# main.net
KiCad netlist of a schematic drawn in EAGLE
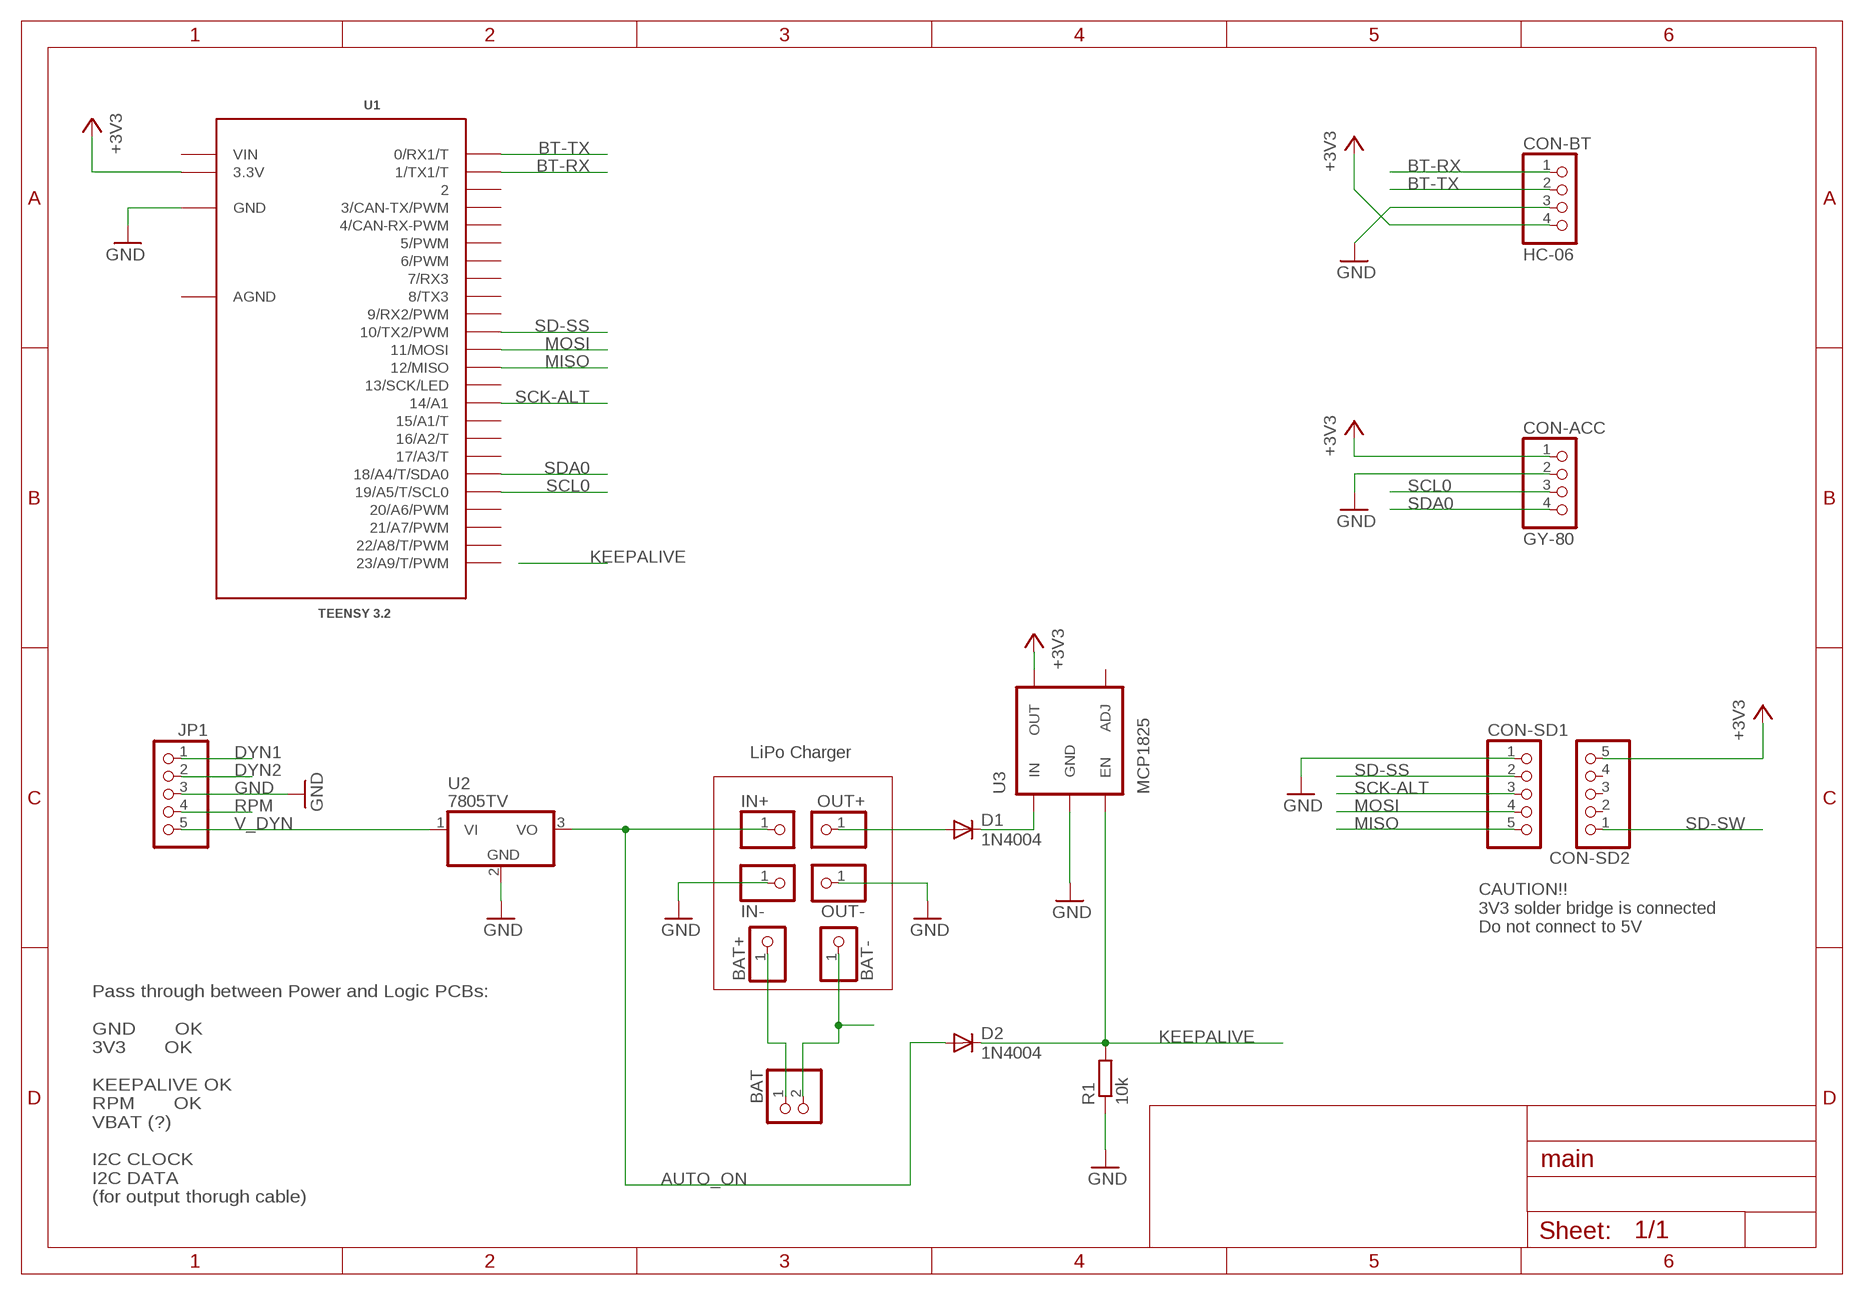
[diagram p0: schematic, sheet 1]

(export (version "E")
  (design (tool "Eeschema 10.0.6"))
  (components
    (comp (ref "BAT")
      (value "PINHD-1X2")
      (footprint "eagle-import:1X02")
      (libsource (lib "eagle-import") (part "PINHD-1X2"))
    )
    (comp (ref "BAT+")
      (value "PINHD-1X1")
      (footprint "eagle-import:1X01")
      (libsource (lib "eagle-import") (part "PINHD-1X1"))
    )
    (comp (ref "BAT-")
      (value "PINHD-1X1")
      (footprint "eagle-import:1X01")
      (libsource (lib "eagle-import") (part "PINHD-1X1"))
    )
    (comp (ref "CON-ACC")
      (value "GY-80")
      (footprint "eagle-import:1X04")
      (libsource (lib "eagle-import") (part "PINHD-1X4"))
    )
    (comp (ref "CON-BT")
      (value "HC-06")
      (footprint "eagle-import:1X04")
      (libsource (lib "eagle-import") (part "PINHD-1X4"))
    )
    (comp (ref "CON-SD1")
      (value "PINHD-1X5")
      (footprint "eagle-import:1X05")
      (libsource (lib "eagle-import") (part "PINHD-1X5"))
    )
    (comp (ref "CON-SD2")
      (value "PINHD-1X5")
      (footprint "eagle-import:1X05")
      (libsource (lib "eagle-import") (part "PINHD-1X5"))
    )
    (comp (ref "D1")
      (value "1N4004")
      (footprint "eagle-import:DO41-10")
      (libsource (lib "eagle-import") (part "1N4004"))
    )
    (comp (ref "D2")
      (value "1N4004")
      (footprint "eagle-import:DO41-10")
      (libsource (lib "eagle-import") (part "1N4004"))
    )
    (comp (ref "IN+")
      (value "PINHD-1X1")
      (footprint "eagle-import:1X01")
      (libsource (lib "eagle-import") (part "PINHD-1X1"))
    )
    (comp (ref "IN-")
      (value "PINHD-1X1")
      (footprint "eagle-import:1X01")
      (libsource (lib "eagle-import") (part "PINHD-1X1"))
    )
    (comp (ref "JP1")
      (value "PINHD-1X5")
      (footprint "eagle-import:1X05")
      (libsource (lib "eagle-import") (part "PINHD-1X5"))
    )
    (comp (ref "OUT+")
      (value "PINHD-1X1")
      (footprint "eagle-import:1X01")
      (libsource (lib "eagle-import") (part "PINHD-1X1"))
    )
    (comp (ref "OUT-")
      (value "PINHD-1X1")
      (footprint "eagle-import:1X01")
      (libsource (lib "eagle-import") (part "PINHD-1X1"))
    )
    (comp (ref "R1")
      (value "10k")
      (footprint "eagle-import:0204_7")
      (libsource (lib "eagle-import") (part "R-EU_0204/7"))
    )
    (comp (ref "U1")
      (value "TEENSY 3.2")
      (footprint "eagle-import:TEENSY3-DIL")
      (libsource (lib "eagle-import") (part "TEENSY_3.1_DIL"))
    )
    (comp (ref "U2")
      (value "7805TV")
      (footprint "eagle-import:TO220V")
      (libsource (lib "eagle-import") (part "78TV05"))
    )
    (comp (ref "U3")
      (value "MCP1825")
      (footprint "eagle-import:SOT23-5")
      (libsource (lib "eagle-import") (part "MCP1824"))
    )
  )
  (nets
    (net (code "1") (name "+3V3") (class "Default")
      (node (ref "CON-ACC") (pin "1") (pinfunction "1_1") (pintype "passive"))
      (node (ref "CON-BT") (pin "4") (pinfunction "4_4") (pintype "passive"))
      (node (ref "CON-SD2") (pin "5") (pinfunction "5_5") (pintype "passive"))
      (node (ref "U1") (pin "3.3V") (pinfunction "3.3V_3.3V") (pintype "power_in"))
      (node (ref "U3") (pin "5") (pinfunction "OUT_5") (pintype "passive"))
    )
    (net (code "2") (name "/AGND") (class "Default")
      (node (ref "U1") (pin "AGND") (pinfunction "AGND_AGND") (pintype "power_in"))
    )
    (net (code "3") (name "/AUTO_ON") (class "Default")
      (node (ref "D2") (pin "A") (pinfunction "A_A") (pintype "passive"))
      (node (ref "IN+") (pin "1") (pinfunction "1_1") (pintype "passive"))
      (node (ref "U2") (pin "3") (pinfunction "VO_3") (pintype "passive"))
    )
    (net (code "4") (name "/BT-RX") (class "Default")
      (node (ref "CON-BT") (pin "1") (pinfunction "1_1") (pintype "passive"))
      (node (ref "U1") (pin "1") (pinfunction "1/TX1/T_1") (pintype "bidirectional"))
    )
    (net (code "5") (name "/BT-TX") (class "Default")
      (node (ref "CON-BT") (pin "2") (pinfunction "2_2") (pintype "passive"))
      (node (ref "U1") (pin "0") (pinfunction "0/RX1/T_0") (pintype "bidirectional"))
    )
    (net (code "6") (name "/DYN1") (class "Default")
      (node (ref "JP1") (pin "1") (pinfunction "1_1") (pintype "passive"))
    )
    (net (code "7") (name "/DYN2") (class "Default")
      (node (ref "JP1") (pin "2") (pinfunction "2_2") (pintype "passive"))
    )
    (net (code "8") (name "/KEEPALIVE") (class "Default")
      (node (ref "D2") (pin "C") (pinfunction "C_C") (pintype "passive"))
      (node (ref "R1") (pin "2") (pinfunction "2_2") (pintype "passive"))
      (node (ref "U3") (pin "3") (pinfunction "EN_3") (pintype "input"))
    )
    (net (code "9") (name "/MISO") (class "Default")
      (node (ref "CON-SD1") (pin "5") (pinfunction "5_5") (pintype "passive"))
      (node (ref "U1") (pin "12") (pinfunction "12/MISO_12") (pintype "bidirectional"))
    )
    (net (code "10") (name "/MOSI") (class "Default")
      (node (ref "CON-SD1") (pin "4") (pinfunction "4_4") (pintype "passive"))
      (node (ref "U1") (pin "11") (pinfunction "11/MOSI_11") (pintype "bidirectional"))
    )
    (net (code "11") (name "/RPM") (class "Default")
      (node (ref "JP1") (pin "4") (pinfunction "4_4") (pintype "passive"))
    )
    (net (code "12") (name "/SCK-ALT") (class "Default")
      (node (ref "CON-SD1") (pin "3") (pinfunction "3_3") (pintype "passive"))
      (node (ref "U1") (pin "14/A0") (pinfunction "14/A1_14/A0") (pintype "bidirectional"))
    )
    (net (code "13") (name "/SCL0") (class "Default")
      (node (ref "CON-ACC") (pin "3") (pinfunction "3_3") (pintype "passive"))
      (node (ref "U1") (pin "19/A5") (pinfunction "19/A5/T/SCL0_19/A5") (pintype "bidirectional"))
    )
    (net (code "14") (name "/SD-SS") (class "Default")
      (node (ref "CON-SD1") (pin "2") (pinfunction "2_2") (pintype "passive"))
      (node (ref "U1") (pin "10") (pinfunction "10/TX2/PWM_10") (pintype "bidirectional"))
    )
    (net (code "15") (name "/SD-SW") (class "Default")
      (node (ref "CON-SD2") (pin "1") (pinfunction "1_1") (pintype "passive"))
    )
    (net (code "16") (name "/SDA0") (class "Default")
      (node (ref "CON-ACC") (pin "4") (pinfunction "4_4") (pintype "passive"))
      (node (ref "U1") (pin "18/A4") (pinfunction "18/A4/T/SDA0_18/A4") (pintype "bidirectional"))
    )
    (net (code "17") (name "/VIN") (class "Default")
      (node (ref "U1") (pin "VIN") (pinfunction "VIN_VIN") (pintype "power_in"))
    )
    (net (code "18") (name "/V_DYN") (class "Default")
      (node (ref "JP1") (pin "5") (pinfunction "5_5") (pintype "passive"))
      (node (ref "U2") (pin "1") (pinfunction "VI_1") (pintype "input"))
    )
    (net (code "19") (name "GND") (class "Default")
      (node (ref "CON-ACC") (pin "2") (pinfunction "2_2") (pintype "passive"))
      (node (ref "CON-BT") (pin "3") (pinfunction "3_3") (pintype "passive"))
      (node (ref "CON-SD1") (pin "1") (pinfunction "1_1") (pintype "passive"))
      (node (ref "IN-") (pin "1") (pinfunction "1_1") (pintype "passive"))
      (node (ref "JP1") (pin "3") (pinfunction "3_3") (pintype "passive"))
      (node (ref "OUT-") (pin "1") (pinfunction "1_1") (pintype "passive"))
      (node (ref "R1") (pin "1") (pinfunction "1_1") (pintype "passive"))
      (node (ref "U1") (pin "GND") (pinfunction "GND_GND") (pintype "power_in"))
      (node (ref "U2") (pin "2") (pinfunction "GND_2") (pintype "passive"))
      (node (ref "U3") (pin "2") (pinfunction "GND_2") (pintype "input"))
    )
    (net (code "20") (name "Net-(BAT+-Pad1)") (class "Default")
      (node (ref "BAT") (pin "1") (pinfunction "1_1") (pintype "passive"))
      (node (ref "BAT+") (pin "1") (pinfunction "1_1") (pintype "passive"))
    )
    (net (code "21") (name "Net-(BAT--Pad1)") (class "Default")
      (node (ref "BAT") (pin "2") (pinfunction "2_2") (pintype "passive"))
      (node (ref "BAT-") (pin "1") (pinfunction "1_1") (pintype "passive"))
    )
    (net (code "22") (name "Net-(D1-PadA)") (class "Default")
      (node (ref "D1") (pin "A") (pinfunction "A_A") (pintype "passive"))
      (node (ref "OUT+") (pin "1") (pinfunction "1_1") (pintype "passive"))
    )
    (net (code "23") (name "Net-(U3-IN)") (class "Default")
      (node (ref "D1") (pin "C") (pinfunction "C_C") (pintype "passive"))
      (node (ref "U3") (pin "1") (pinfunction "IN_1") (pintype "input"))
    )
    (net (code "24") (name "unconnected-(CON-SD2-Pad2)") (class "Default")
      (node (ref "CON-SD2") (pin "2") (pinfunction "2_2") (pintype "passive"))
    )
    (net (code "25") (name "unconnected-(CON-SD2-Pad3)") (class "Default")
      (node (ref "CON-SD2") (pin "3") (pinfunction "3_3") (pintype "passive"))
    )
    (net (code "26") (name "unconnected-(CON-SD2-Pad4)") (class "Default")
      (node (ref "CON-SD2") (pin "4") (pinfunction "4_4") (pintype "passive"))
    )
    (net (code "27") (name "unconnected-(U1-3{slash}CAN-TX{slash}PWM-Pad3)") (class "Default")
      (node (ref "U1") (pin "3") (pinfunction "3/CAN-TX/PWM_3") (pintype "bidirectional"))
    )
    (net (code "28") (name "unconnected-(U1-4{slash}CAN-RX-PWM-Pad4)") (class "Default")
      (node (ref "U1") (pin "4") (pinfunction "4/CAN-RX-PWM_4") (pintype "bidirectional"))
    )
    (net (code "29") (name "unconnected-(U1-5{slash}PWM-Pad5)") (class "Default")
      (node (ref "U1") (pin "5") (pinfunction "5/PWM_5") (pintype "bidirectional"))
    )
    (net (code "30") (name "unconnected-(U1-6{slash}PWM-Pad6)") (class "Default")
      (node (ref "U1") (pin "6") (pinfunction "6/PWM_6") (pintype "bidirectional"))
    )
    (net (code "31") (name "unconnected-(U1-7{slash}RX3-Pad7)") (class "Default")
      (node (ref "U1") (pin "7") (pinfunction "7/RX3_7") (pintype "bidirectional"))
    )
    (net (code "32") (name "unconnected-(U1-8{slash}TX3-Pad8)") (class "Default")
      (node (ref "U1") (pin "8") (pinfunction "8/TX3_8") (pintype "bidirectional"))
    )
    (net (code "33") (name "unconnected-(U1-9{slash}RX2{slash}PWM-Pad9)") (class "Default")
      (node (ref "U1") (pin "9") (pinfunction "9/RX2/PWM_9") (pintype "bidirectional"))
    )
    (net (code "34") (name "unconnected-(U1-13{slash}SCK{slash}LED-Pad13)") (class "Default")
      (node (ref "U1") (pin "13") (pinfunction "13/SCK/LED_13") (pintype "bidirectional"))
    )
    (net (code "35") (name "unconnected-(U1-15{slash}A1{slash}T-Pad15{slash}A1)") (class "Default")
      (node (ref "U1") (pin "15/A1") (pinfunction "15/A1/T_15/A1") (pintype "bidirectional"))
    )
    (net (code "36") (name "unconnected-(U1-16{slash}A2{slash}T-Pad16{slash}A2)") (class "Default")
      (node (ref "U1") (pin "16/A2") (pinfunction "16/A2/T_16/A2") (pintype "bidirectional"))
    )
    (net (code "37") (name "unconnected-(U1-17{slash}A3{slash}T-Pad17{slash}A3)") (class "Default")
      (node (ref "U1") (pin "17/A3") (pinfunction "17/A3/T_17/A3") (pintype "bidirectional"))
    )
    (net (code "38") (name "unconnected-(U1-20{slash}A6{slash}PWM-Pad20{slash}A6)") (class "Default")
      (node (ref "U1") (pin "20/A6") (pinfunction "20/A6/PWM_20/A6") (pintype "bidirectional"))
    )
    (net (code "39") (name "unconnected-(U1-21{slash}A7{slash}PWM-Pad21{slash}A7)") (class "Default")
      (node (ref "U1") (pin "21/A7") (pinfunction "21/A7/PWM_21/A7") (pintype "bidirectional"))
    )
    (net (code "40") (name "unconnected-(U1-22{slash}A8{slash}T{slash}PWM-Pad22{slash}A8)") (class "Default")
      (node (ref "U1") (pin "22/A8") (pinfunction "22/A8/T/PWM_22/A8") (pintype "bidirectional"))
    )
    (net (code "41") (name "unconnected-(U1-23{slash}A9{slash}T{slash}PWM-Pad23{slash}A9)") (class "Default")
      (node (ref "U1") (pin "23/A9") (pinfunction "23/A9/T/PWM_23/A9") (pintype "bidirectional"))
    )
    (net (code "42") (name "unconnected-(U1-Pad2)") (class "Default")
      (node (ref "U1") (pin "2") (pinfunction "2_2") (pintype "bidirectional"))
    )
    (net (code "43") (name "unconnected-(U3-ADJ-Pad4)") (class "Default")
      (node (ref "U3") (pin "4") (pinfunction "ADJ_4") (pintype "input"))
    )
  )
)
